# floppy_emul.net
KiCad netlist of a schematic drawn in EAGLE
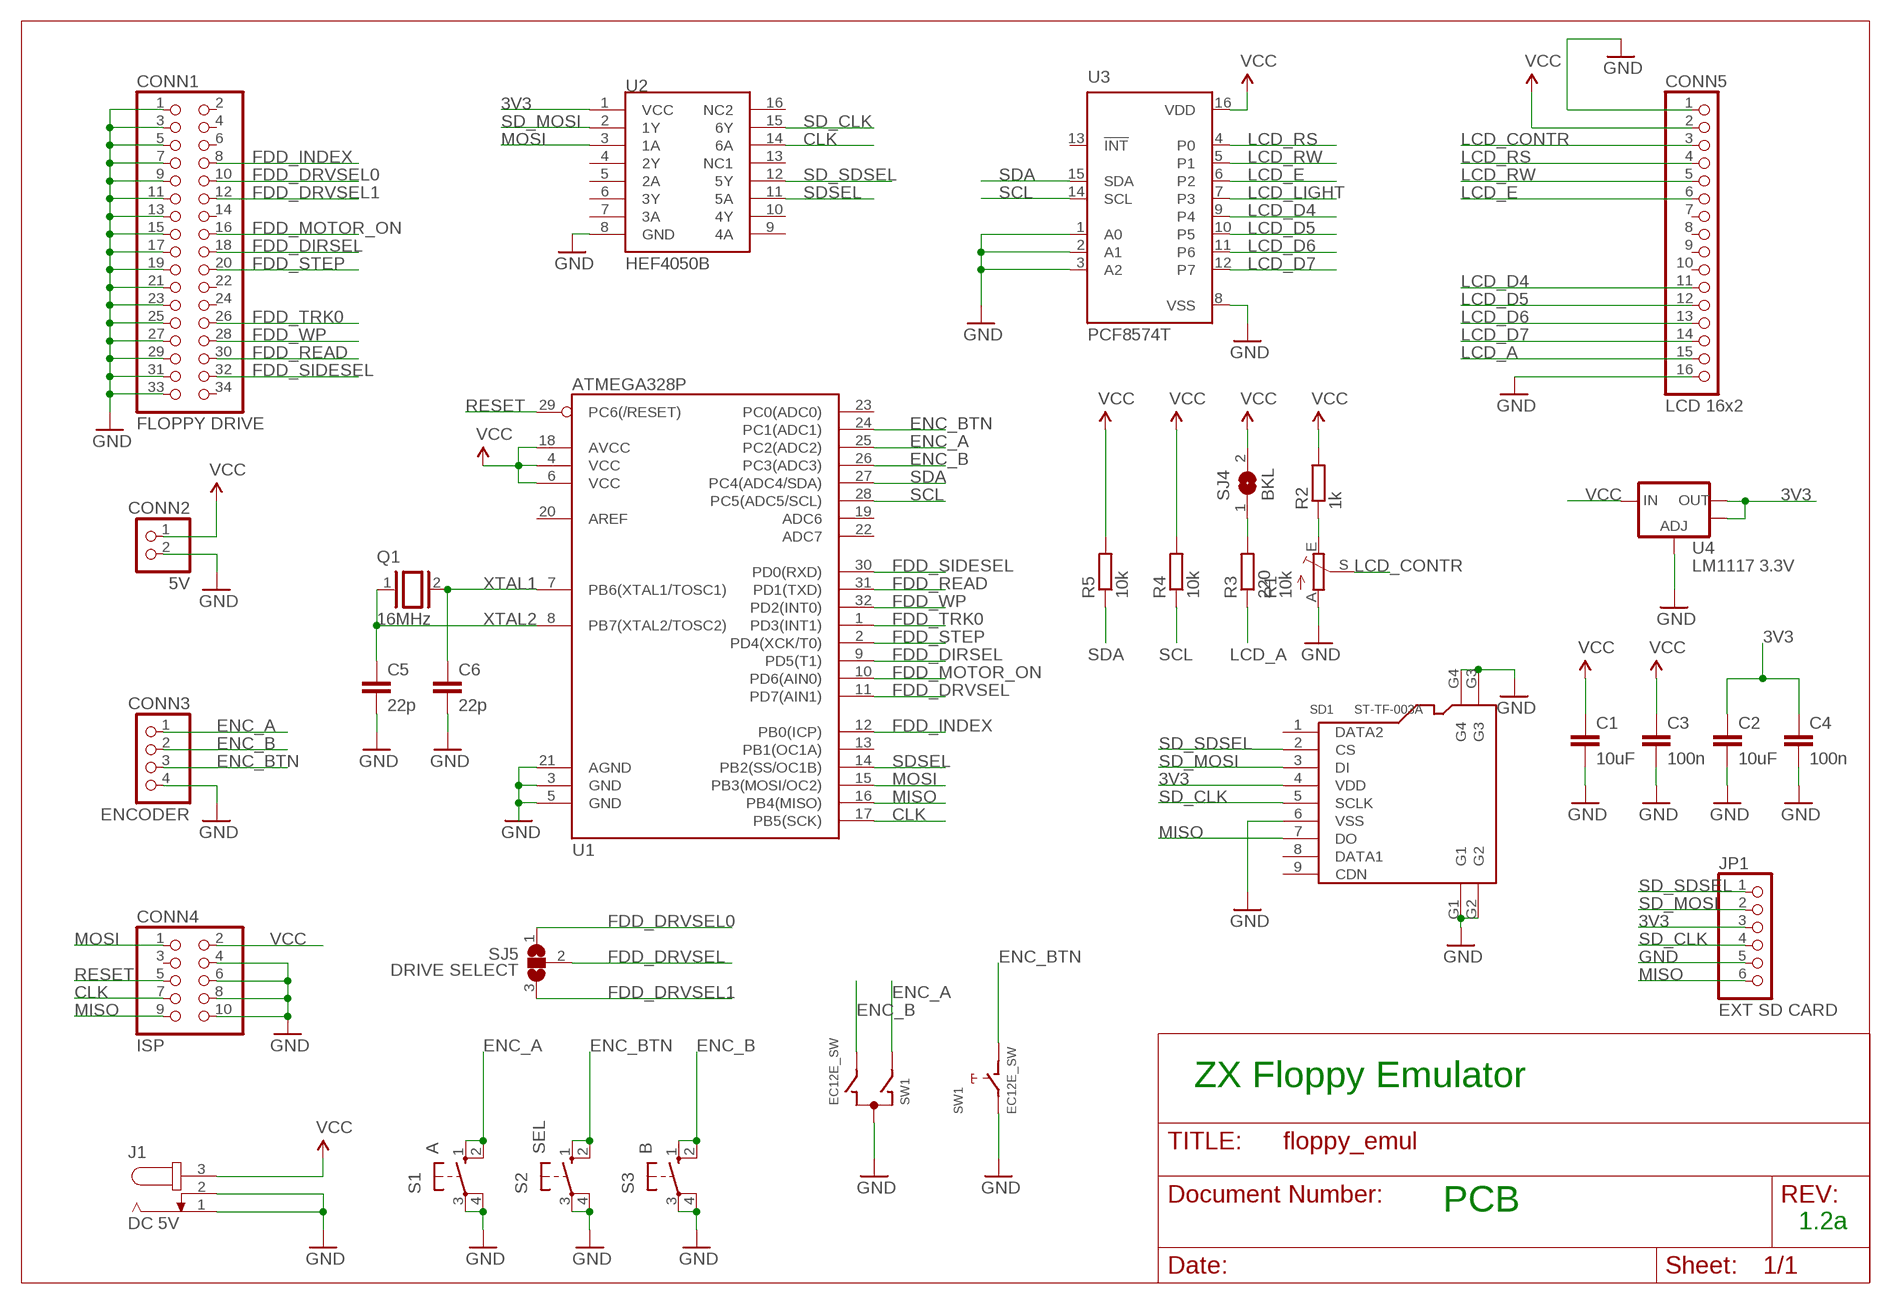
[diagram p0: schematic, sheet 1]

(export (version "E")
  (design (tool "Eeschema 10.0.6"))
  (components
    (comp (ref "C1")
      (value "10uF")
      (footprint "eagle-import:C0805")
      (libsource (lib "eagle-import") (part "C-EUC0805"))
    )
    (comp (ref "C2")
      (value "10uF")
      (footprint "eagle-import:C0805")
      (libsource (lib "eagle-import") (part "C-EUC0805"))
    )
    (comp (ref "C3")
      (value "100n")
      (footprint "eagle-import:C0805")
      (libsource (lib "eagle-import") (part "C-EUC0805"))
    )
    (comp (ref "C4")
      (value "100n")
      (footprint "eagle-import:C0805")
      (libsource (lib "eagle-import") (part "C-EUC0805"))
    )
    (comp (ref "C5")
      (value "22p")
      (footprint "eagle-import:C0805")
      (libsource (lib "eagle-import") (part "C-EUC0805"))
    )
    (comp (ref "C6")
      (value "22p")
      (footprint "eagle-import:C0805")
      (libsource (lib "eagle-import") (part "C-EUC0805"))
    )
    (comp (ref "CONN1")
      (value "FLOPPY DRIVE")
      (footprint "eagle-import:2X17")
      (libsource (lib "eagle-import") (part "PINHD-2X17"))
    )
    (comp (ref "CONN2")
      (value "5V")
      (footprint "eagle-import:1X02")
      (libsource (lib "eagle-import") (part "PINHD-1X2"))
    )
    (comp (ref "CONN3")
      (value "ENCODER")
      (footprint "eagle-import:1X04")
      (libsource (lib "eagle-import") (part "PINHD-1X4"))
    )
    (comp (ref "CONN4")
      (value "ISP")
      (footprint "eagle-import:2X05")
      (libsource (lib "eagle-import") (part "PINHD-2X5_2.54"))
    )
    (comp (ref "CONN5")
      (value "LCD 16x2")
      (footprint "eagle-import:1X16")
      (libsource (lib "eagle-import") (part "PINHD-1X16"))
    )
    (comp (ref "J1")
      (value "DC 5V")
      (footprint "eagle-import:SPC4077")
      (libsource (lib "eagle-import") (part "JACK-PLUG0"))
    )
    (comp (ref "JP1")
      (value "EXT SD CARD")
      (footprint "eagle-import:1X06")
      (libsource (lib "eagle-import") (part "PINHD-1X6"))
    )
    (comp (ref "Q1")
      (value "16MHz")
      (footprint "eagle-import:QS")
      (libsource (lib "eagle-import") (part "XTAL/S"))
    )
    (comp (ref "R1")
      (value "10k")
      (footprint "eagle-import:RJ9W")
      (libsource (lib "eagle-import") (part "TRIM_EU-RJ9W"))
    )
    (comp (ref "R2")
      (value "1k")
      (footprint "eagle-import:R0805")
      (libsource (lib "eagle-import") (part "R-EU_R0805"))
    )
    (comp (ref "R3")
      (value "220")
      (footprint "eagle-import:R0805")
      (libsource (lib "eagle-import") (part "R-EU_R0805"))
    )
    (comp (ref "R4")
      (value "10k")
      (footprint "eagle-import:R0805")
      (libsource (lib "eagle-import") (part "R-EU_R0805"))
    )
    (comp (ref "R5")
      (value "10k")
      (footprint "eagle-import:R0805")
      (libsource (lib "eagle-import") (part "R-EU_R0805"))
    )
    (comp (ref "S1")
      (value "A")
      (footprint "eagle-import:B3F-10XX")
      (fields (field (name "MPN") "B3F-1000"))
      (libsource (lib "eagle-import") (part "10-XX"))
    )
    (comp (ref "S2")
      (value "SEL")
      (footprint "eagle-import:B3F-10XX")
      (fields (field (name "MPN") "B3F-1000"))
      (libsource (lib "eagle-import") (part "10-XX"))
    )
    (comp (ref "S3")
      (value "B")
      (footprint "eagle-import:B3F-10XX")
      (fields (field (name "MPN") "B3F-1000"))
      (libsource (lib "eagle-import") (part "10-XX"))
    )
    (comp (ref "SD1")
      (value "ST-TF-003A")
      (footprint "eagle-import:MICRO-SD9+4P-SMD-16.1X14.5X1.85MM")
      (libsource (lib "eagle-import") (part "MICRO-SD-CARD-SOCKET-9P(ST-TF-003A)"))
    )
    (comp (ref "SJ4")
      (value "BKL")
      (footprint "eagle-import:SJ")
      (libsource (lib "eagle-import") (part "SJ"))
    )
    (comp (ref "SJ5")
      (value "DRIVE SELECT")
      (footprint "eagle-import:SJ_2")
      (libsource (lib "eagle-import") (part "SJ2W"))
    )
    (comp (ref "SW1")
      (value "EC12E_SW")
      (footprint "eagle-import:ALPS_EC12E_SW")
      (fields (field (name "MPN") "EC12E2424407"))
      (libsource (lib "eagle-import") (part "EC12E_SW"))
    )
    (comp (ref "U1")
      (value "ATMEGA328P")
      (footprint "eagle-import:TQFP32-08")
      (libsource (lib "eagle-import") (part "ATMEGA328_SMT"))
    )
    (comp (ref "U2")
      (value "HEF4050B")
      (footprint "eagle-import:SO16")
      (libsource (lib "eagle-import") (part "HEF4050BSO16"))
    )
    (comp (ref "U3")
      (value "PCF8574T")
      (footprint "eagle-import:SO16W")
      (fields (field (name "MPN") "PCF8574T/3,512"))
      (libsource (lib "eagle-import") (part "PCF8574T"))
    )
    (comp (ref "U4")
      (value "LM1117 3.3V")
      (footprint "eagle-import:SOT223")
      (libsource (lib "eagle-import") (part "V_REG_LM1117SOT223"))
    )
  )
  (nets
    (net (code "1") (name "/3V3") (class "Default")
      (node (ref "C2") (pin "1") (pinfunction "1_1") (pintype "passive"))
      (node (ref "C4") (pin "1") (pinfunction "1_1") (pintype "passive"))
      (node (ref "JP1") (pin "3") (pinfunction "3_3") (pintype "passive"))
      (node (ref "SD1") (pin "4") (pinfunction "VDD_4") (pintype "bidirectional"))
      (node (ref "U2") (pin "1") (pinfunction "VCC_1") (pintype "power_in"))
      (node (ref "U4") (pin "2") (pinfunction "OUT_2") (pintype "output"))
      (node (ref "U4") (pin "4") (pinfunction "OUT_4") (pintype "output"))
    )
    (net (code "2") (name "/CLK") (class "Default")
      (node (ref "CONN4") (pin "7") (pinfunction "7_7") (pintype "passive"))
      (node (ref "U1") (pin "17") (pinfunction "PB5(SCK)_17") (pintype "bidirectional"))
      (node (ref "U2") (pin "14") (pinfunction "6A_14") (pintype "input"))
    )
    (net (code "3") (name "/ENC_A") (class "Default")
      (node (ref "CONN3") (pin "1") (pinfunction "1_1") (pintype "passive"))
      (node (ref "S1") (pin "1") (pinfunction "S_1") (pintype "passive"))
      (node (ref "S1") (pin "2") (pinfunction "S1_2") (pintype "passive"))
      (node (ref "SW1") (pin "A") (pinfunction "A_A") (pintype "passive"))
      (node (ref "U1") (pin "25") (pinfunction "PC2(ADC2)_25") (pintype "bidirectional"))
    )
    (net (code "4") (name "/ENC_B") (class "Default")
      (node (ref "CONN3") (pin "2") (pinfunction "2_2") (pintype "passive"))
      (node (ref "S3") (pin "1") (pinfunction "S_1") (pintype "passive"))
      (node (ref "S3") (pin "2") (pinfunction "S1_2") (pintype "passive"))
      (node (ref "SW1") (pin "B") (pinfunction "B_B") (pintype "passive"))
      (node (ref "U1") (pin "26") (pinfunction "PC3(ADC3)_26") (pintype "bidirectional"))
    )
    (net (code "5") (name "/ENC_BTN") (class "Default")
      (node (ref "CONN3") (pin "3") (pinfunction "3_3") (pintype "passive"))
      (node (ref "S2") (pin "1") (pinfunction "S_1") (pintype "passive"))
      (node (ref "S2") (pin "2") (pinfunction "S1_2") (pintype "passive"))
      (node (ref "SW1") (pin "D") (pinfunction "1_D") (pintype "passive"))
      (node (ref "U1") (pin "24") (pinfunction "PC1(ADC1)_24") (pintype "bidirectional"))
    )
    (net (code "6") (name "/FDD_DIRSEL") (class "Default")
      (node (ref "CONN1") (pin "18") (pinfunction "18_18") (pintype "passive"))
      (node (ref "U1") (pin "9") (pinfunction "PD5(T1)_9") (pintype "bidirectional"))
    )
    (net (code "7") (name "/FDD_DRVSEL") (class "Default")
      (node (ref "SJ5") (pin "2") (pinfunction "2_2") (pintype "passive"))
      (node (ref "U1") (pin "11") (pinfunction "PD7(AIN1)_11") (pintype "bidirectional"))
    )
    (net (code "8") (name "/FDD_DRVSEL0") (class "Default")
      (node (ref "CONN1") (pin "10") (pinfunction "10_10") (pintype "passive"))
      (node (ref "SJ5") (pin "1") (pinfunction "1_1") (pintype "passive"))
    )
    (net (code "9") (name "/FDD_DRVSEL1") (class "Default")
      (node (ref "CONN1") (pin "12") (pinfunction "12_12") (pintype "passive"))
      (node (ref "SJ5") (pin "3") (pinfunction "3_3") (pintype "passive"))
    )
    (net (code "10") (name "/FDD_INDEX") (class "Default")
      (node (ref "CONN1") (pin "8") (pinfunction "8_8") (pintype "passive"))
      (node (ref "U1") (pin "12") (pinfunction "PB0(ICP)_12") (pintype "bidirectional"))
    )
    (net (code "11") (name "/FDD_MOTOR_ON") (class "Default")
      (node (ref "CONN1") (pin "16") (pinfunction "16_16") (pintype "passive"))
      (node (ref "U1") (pin "10") (pinfunction "PD6(AIN0)_10") (pintype "bidirectional"))
    )
    (net (code "12") (name "/FDD_READ") (class "Default")
      (node (ref "CONN1") (pin "30") (pinfunction "30_30") (pintype "passive"))
      (node (ref "U1") (pin "31") (pinfunction "PD1(TXD)_31") (pintype "bidirectional"))
    )
    (net (code "13") (name "/FDD_SIDESEL") (class "Default")
      (node (ref "CONN1") (pin "32") (pinfunction "32_32") (pintype "passive"))
      (node (ref "U1") (pin "30") (pinfunction "PD0(RXD)_30") (pintype "bidirectional"))
    )
    (net (code "14") (name "/FDD_STEP") (class "Default")
      (node (ref "CONN1") (pin "20") (pinfunction "20_20") (pintype "passive"))
      (node (ref "U1") (pin "2") (pinfunction "PD4(XCK/T0)_2") (pintype "bidirectional"))
    )
    (net (code "15") (name "/FDD_TRK0") (class "Default")
      (node (ref "CONN1") (pin "26") (pinfunction "26_26") (pintype "passive"))
      (node (ref "U1") (pin "1") (pinfunction "PD3(INT1)_1") (pintype "bidirectional"))
    )
    (net (code "16") (name "/FDD_WP") (class "Default")
      (node (ref "CONN1") (pin "28") (pinfunction "28_28") (pintype "passive"))
      (node (ref "U1") (pin "32") (pinfunction "PD2(INT0)_32") (pintype "bidirectional"))
    )
    (net (code "17") (name "/LCD_A") (class "Default")
      (node (ref "CONN5") (pin "15") (pinfunction "15_15") (pintype "passive"))
      (node (ref "R3") (pin "1") (pinfunction "1_1") (pintype "passive"))
    )
    (net (code "18") (name "/LCD_CONTR") (class "Default")
      (node (ref "CONN5") (pin "3") (pinfunction "3_3") (pintype "passive"))
      (node (ref "R1") (pin "S") (pinfunction "S_S") (pintype "passive"))
    )
    (net (code "19") (name "/LCD_D4") (class "Default")
      (node (ref "CONN5") (pin "11") (pinfunction "11_11") (pintype "passive"))
      (node (ref "U3") (pin "9") (pinfunction "P4_9") (pintype "bidirectional"))
    )
    (net (code "20") (name "/LCD_D5") (class "Default")
      (node (ref "CONN5") (pin "12") (pinfunction "12_12") (pintype "passive"))
      (node (ref "U3") (pin "10") (pinfunction "P5_10") (pintype "bidirectional"))
    )
    (net (code "21") (name "/LCD_D6") (class "Default")
      (node (ref "CONN5") (pin "13") (pinfunction "13_13") (pintype "passive"))
      (node (ref "U3") (pin "11") (pinfunction "P6_11") (pintype "bidirectional"))
    )
    (net (code "22") (name "/LCD_D7") (class "Default")
      (node (ref "CONN5") (pin "14") (pinfunction "14_14") (pintype "passive"))
      (node (ref "U3") (pin "12") (pinfunction "P7_12") (pintype "bidirectional"))
    )
    (net (code "23") (name "/LCD_E") (class "Default")
      (node (ref "CONN5") (pin "6") (pinfunction "6_6") (pintype "passive"))
      (node (ref "U3") (pin "6") (pinfunction "P2_6") (pintype "bidirectional"))
    )
    (net (code "24") (name "/LCD_LIGHT") (class "Default")
      (node (ref "U3") (pin "7") (pinfunction "P3_7") (pintype "bidirectional"))
    )
    (net (code "25") (name "/LCD_RS") (class "Default")
      (node (ref "CONN5") (pin "4") (pinfunction "4_4") (pintype "passive"))
      (node (ref "U3") (pin "4") (pinfunction "P0_4") (pintype "bidirectional"))
    )
    (net (code "26") (name "/LCD_RW") (class "Default")
      (node (ref "CONN5") (pin "5") (pinfunction "5_5") (pintype "passive"))
      (node (ref "U3") (pin "5") (pinfunction "P1_5") (pintype "bidirectional"))
    )
    (net (code "27") (name "/MISO") (class "Default")
      (node (ref "CONN4") (pin "9") (pinfunction "9_9") (pintype "passive"))
      (node (ref "JP1") (pin "6") (pinfunction "6_6") (pintype "passive"))
      (node (ref "SD1") (pin "7") (pinfunction "DO_7") (pintype "bidirectional"))
      (node (ref "U1") (pin "16") (pinfunction "PB4(MISO)_16") (pintype "bidirectional"))
    )
    (net (code "28") (name "/MOSI") (class "Default")
      (node (ref "CONN4") (pin "1") (pinfunction "1_1") (pintype "passive"))
      (node (ref "U1") (pin "15") (pinfunction "PB3(MOSI/OC2)_15") (pintype "bidirectional"))
      (node (ref "U2") (pin "3") (pinfunction "1A_3") (pintype "input"))
    )
    (net (code "29") (name "/RESET") (class "Default")
      (node (ref "CONN4") (pin "5") (pinfunction "5_5") (pintype "passive"))
      (node (ref "U1") (pin "29") (pinfunction "PC6(/RESET)_29") (pintype "bidirectional"))
    )
    (net (code "30") (name "/SCL") (class "Default")
      (node (ref "R4") (pin "1") (pinfunction "1_1") (pintype "passive"))
      (node (ref "U1") (pin "28") (pinfunction "PC5(ADC5/SCL)_28") (pintype "bidirectional"))
      (node (ref "U3") (pin "14") (pinfunction "SCL_14") (pintype "input"))
    )
    (net (code "31") (name "/SDA") (class "Default")
      (node (ref "R5") (pin "1") (pinfunction "1_1") (pintype "passive"))
      (node (ref "U1") (pin "27") (pinfunction "PC4(ADC4/SDA)_27") (pintype "bidirectional"))
      (node (ref "U3") (pin "15") (pinfunction "SDA_15") (pintype "bidirectional"))
    )
    (net (code "32") (name "/SDSEL") (class "Default")
      (node (ref "U1") (pin "14") (pinfunction "PB2(SS/OC1B)_14") (pintype "bidirectional"))
      (node (ref "U2") (pin "11") (pinfunction "5A_11") (pintype "input"))
    )
    (net (code "33") (name "/SD_CLK") (class "Default")
      (node (ref "JP1") (pin "4") (pinfunction "4_4") (pintype "passive"))
      (node (ref "SD1") (pin "5") (pinfunction "SCLK_5") (pintype "bidirectional"))
      (node (ref "U2") (pin "15") (pinfunction "6Y_15") (pintype "output"))
    )
    (net (code "34") (name "/SD_MOSI") (class "Default")
      (node (ref "JP1") (pin "2") (pinfunction "2_2") (pintype "passive"))
      (node (ref "SD1") (pin "3") (pinfunction "DI_3") (pintype "bidirectional"))
      (node (ref "U2") (pin "2") (pinfunction "1Y_2") (pintype "output"))
    )
    (net (code "35") (name "/SD_SDSEL") (class "Default")
      (node (ref "JP1") (pin "1") (pinfunction "1_1") (pintype "passive"))
      (node (ref "SD1") (pin "2") (pinfunction "CS_2") (pintype "bidirectional"))
      (node (ref "U2") (pin "12") (pinfunction "5Y_12") (pintype "output"))
    )
    (net (code "36") (name "/XTAL1") (class "Default")
      (node (ref "C6") (pin "1") (pinfunction "1_1") (pintype "passive"))
      (node (ref "Q1") (pin "2") (pinfunction "2_2") (pintype "passive"))
      (node (ref "U1") (pin "7") (pinfunction "PB6(XTAL1/TOSC1)_7") (pintype "bidirectional"))
    )
    (net (code "37") (name "/XTAL2") (class "Default")
      (node (ref "C5") (pin "1") (pinfunction "1_1") (pintype "passive"))
      (node (ref "Q1") (pin "1") (pinfunction "1_1") (pintype "passive"))
      (node (ref "U1") (pin "8") (pinfunction "PB7(XTAL2/TOSC2)_8") (pintype "bidirectional"))
    )
    (net (code "38") (name "GND") (class "Default")
      (node (ref "C1") (pin "2") (pinfunction "2_2") (pintype "passive"))
      (node (ref "C2") (pin "2") (pinfunction "2_2") (pintype "passive"))
      (node (ref "C3") (pin "2") (pinfunction "2_2") (pintype "passive"))
      (node (ref "C4") (pin "2") (pinfunction "2_2") (pintype "passive"))
      (node (ref "C5") (pin "2") (pinfunction "2_2") (pintype "passive"))
      (node (ref "C6") (pin "2") (pinfunction "2_2") (pintype "passive"))
      (node (ref "CONN1") (pin "1") (pinfunction "1_1") (pintype "passive"))
      (node (ref "CONN1") (pin "11") (pinfunction "11_11") (pintype "passive"))
      (node (ref "CONN1") (pin "13") (pinfunction "13_13") (pintype "passive"))
      (node (ref "CONN1") (pin "15") (pinfunction "15_15") (pintype "passive"))
      (node (ref "CONN1") (pin "17") (pinfunction "17_17") (pintype "passive"))
      (node (ref "CONN1") (pin "19") (pinfunction "19_19") (pintype "passive"))
      (node (ref "CONN1") (pin "21") (pinfunction "21_21") (pintype "passive"))
      (node (ref "CONN1") (pin "23") (pinfunction "23_23") (pintype "passive"))
      (node (ref "CONN1") (pin "25") (pinfunction "25_25") (pintype "passive"))
      (node (ref "CONN1") (pin "27") (pinfunction "27_27") (pintype "passive"))
      (node (ref "CONN1") (pin "29") (pinfunction "29_29") (pintype "passive"))
      (node (ref "CONN1") (pin "3") (pinfunction "3_3") (pintype "passive"))
      (node (ref "CONN1") (pin "31") (pinfunction "31_31") (pintype "passive"))
      (node (ref "CONN1") (pin "33") (pinfunction "33_33") (pintype "passive"))
      (node (ref "CONN1") (pin "5") (pinfunction "5_5") (pintype "passive"))
      (node (ref "CONN1") (pin "7") (pinfunction "7_7") (pintype "passive"))
      (node (ref "CONN1") (pin "9") (pinfunction "9_9") (pintype "passive"))
      (node (ref "CONN2") (pin "2") (pinfunction "2_2") (pintype "passive"))
      (node (ref "CONN3") (pin "4") (pinfunction "4_4") (pintype "passive"))
      (node (ref "CONN4") (pin "10") (pinfunction "10_10") (pintype "passive"))
      (node (ref "CONN4") (pin "4") (pinfunction "4_4") (pintype "passive"))
      (node (ref "CONN4") (pin "6") (pinfunction "6_6") (pintype "passive"))
      (node (ref "CONN4") (pin "8") (pinfunction "8_8") (pintype "passive"))
      (node (ref "CONN5") (pin "1") (pinfunction "1_1") (pintype "passive"))
      (node (ref "CONN5") (pin "16") (pinfunction "16_16") (pintype "passive"))
      (node (ref "J1") (pin "1") (pinfunction "1_1") (pintype "passive"))
      (node (ref "J1") (pin "2") (pinfunction "2_2") (pintype "passive"))
      (node (ref "JP1") (pin "5") (pinfunction "5_5") (pintype "passive"))
      (node (ref "R1") (pin "A") (pinfunction "A_A") (pintype "passive"))
      (node (ref "S1") (pin "3") (pinfunction "P_3") (pintype "passive"))
      (node (ref "S1") (pin "4") (pinfunction "P1_4") (pintype "passive"))
      (node (ref "S2") (pin "3") (pinfunction "P_3") (pintype "passive"))
      (node (ref "S2") (pin "4") (pinfunction "P1_4") (pintype "passive"))
      (node (ref "S3") (pin "3") (pinfunction "P_3") (pintype "passive"))
      (node (ref "S3") (pin "4") (pinfunction "P1_4") (pintype "passive"))
      (node (ref "SD1") (pin "6") (pinfunction "VSS_6") (pintype "bidirectional"))
      (node (ref "SD1") (pin "G1") (pinfunction "G1_G1") (pintype "bidirectional"))
      (node (ref "SD1") (pin "G2") (pinfunction "G2_G2") (pintype "bidirectional"))
      (node (ref "SD1") (pin "G3") (pinfunction "G3_G3") (pintype "bidirectional"))
      (node (ref "SD1") (pin "G4") (pinfunction "G4_G4") (pintype "bidirectional"))
      (node (ref "SW1") (pin "C") (pinfunction "C_C") (pintype "passive"))
      (node (ref "SW1") (pin "E") (pinfunction "2_E") (pintype "passive"))
      (node (ref "U1") (pin "21") (pinfunction "AGND_21") (pintype "bidirectional"))
      (node (ref "U1") (pin "3") (pinfunction "GND_3") (pintype "bidirectional"))
      (node (ref "U1") (pin "5") (pinfunction "GND_5") (pintype "bidirectional"))
      (node (ref "U2") (pin "8") (pinfunction "GND_8") (pintype "power_in"))
      (node (ref "U3") (pin "1") (pinfunction "A0_1") (pintype "input"))
      (node (ref "U3") (pin "2") (pinfunction "A1_2") (pintype "input"))
      (node (ref "U3") (pin "3") (pinfunction "A2_3") (pintype "input"))
      (node (ref "U3") (pin "8") (pinfunction "VSS_8") (pintype "power_in"))
      (node (ref "U4") (pin "1") (pinfunction "ADJ_1") (pintype "input"))
    )
    (net (code "39") (name "Net-(R1-PadE)") (class "Default")
      (node (ref "R1") (pin "E") (pinfunction "E_E") (pintype "passive"))
      (node (ref "R2") (pin "1") (pinfunction "1_1") (pintype "passive"))
    )
    (net (code "40") (name "Net-(R3-Pad2)") (class "Default")
      (node (ref "R3") (pin "2") (pinfunction "2_2") (pintype "passive"))
      (node (ref "SJ4") (pin "1") (pinfunction "1_1") (pintype "passive"))
    )
    (net (code "41") (name "VCC") (class "Default")
      (node (ref "C1") (pin "1") (pinfunction "1_1") (pintype "passive"))
      (node (ref "C3") (pin "1") (pinfunction "1_1") (pintype "passive"))
      (node (ref "CONN2") (pin "1") (pinfunction "1_1") (pintype "passive"))
      (node (ref "CONN4") (pin "2") (pinfunction "2_2") (pintype "passive"))
      (node (ref "CONN5") (pin "2") (pinfunction "2_2") (pintype "passive"))
      (node (ref "J1") (pin "3") (pinfunction "3_3") (pintype "passive"))
      (node (ref "R2") (pin "2") (pinfunction "2_2") (pintype "passive"))
      (node (ref "R4") (pin "2") (pinfunction "2_2") (pintype "passive"))
      (node (ref "R5") (pin "2") (pinfunction "2_2") (pintype "passive"))
      (node (ref "SJ4") (pin "2") (pinfunction "2_2") (pintype "passive"))
      (node (ref "U1") (pin "18") (pinfunction "AVCC_18") (pintype "bidirectional"))
      (node (ref "U1") (pin "4") (pinfunction "VCC_4") (pintype "bidirectional"))
      (node (ref "U1") (pin "6") (pinfunction "VCC_6") (pintype "bidirectional"))
      (node (ref "U3") (pin "16") (pinfunction "VDD_16") (pintype "power_in"))
      (node (ref "U4") (pin "3") (pinfunction "IN_3") (pintype "input"))
    )
    (net (code "42") (name "unconnected-(CONN1-Pad2)") (class "Default")
      (node (ref "CONN1") (pin "2") (pinfunction "2_2") (pintype "passive"))
    )
    (net (code "43") (name "unconnected-(CONN1-Pad4)") (class "Default")
      (node (ref "CONN1") (pin "4") (pinfunction "4_4") (pintype "passive"))
    )
    (net (code "44") (name "unconnected-(CONN1-Pad6)") (class "Default")
      (node (ref "CONN1") (pin "6") (pinfunction "6_6") (pintype "passive"))
    )
    (net (code "45") (name "unconnected-(CONN1-Pad14)") (class "Default")
      (node (ref "CONN1") (pin "14") (pinfunction "14_14") (pintype "passive"))
    )
    (net (code "46") (name "unconnected-(CONN1-Pad22)") (class "Default")
      (node (ref "CONN1") (pin "22") (pinfunction "22_22") (pintype "passive"))
    )
    (net (code "47") (name "unconnected-(CONN1-Pad24)") (class "Default")
      (node (ref "CONN1") (pin "24") (pinfunction "24_24") (pintype "passive"))
    )
    (net (code "48") (name "unconnected-(CONN1-Pad34)") (class "Default")
      (node (ref "CONN1") (pin "34") (pinfunction "34_34") (pintype "passive"))
    )
    (net (code "49") (name "unconnected-(CONN4-Pad3)") (class "Default")
      (node (ref "CONN4") (pin "3") (pinfunction "3_3") (pintype "passive"))
    )
    (net (code "50") (name "unconnected-(CONN5-Pad7)") (class "Default")
      (node (ref "CONN5") (pin "7") (pinfunction "7_7") (pintype "passive"))
    )
    (net (code "51") (name "unconnected-(CONN5-Pad8)") (class "Default")
      (node (ref "CONN5") (pin "8") (pinfunction "8_8") (pintype "passive"))
    )
    (net (code "52") (name "unconnected-(CONN5-Pad9)") (class "Default")
      (node (ref "CONN5") (pin "9") (pinfunction "9_9") (pintype "passive"))
    )
    (net (code "53") (name "unconnected-(CONN5-Pad10)") (class "Default")
      (node (ref "CONN5") (pin "10") (pinfunction "10_10") (pintype "passive"))
    )
    (net (code "54") (name "unconnected-(SD1-CDN-Pad9)") (class "Default")
      (node (ref "SD1") (pin "9") (pinfunction "CDN_9") (pintype "bidirectional"))
    )
    (net (code "55") (name "unconnected-(SD1-DATA1-Pad8)") (class "Default")
      (node (ref "SD1") (pin "8") (pinfunction "DATA1_8") (pintype "bidirectional"))
    )
    (net (code "56") (name "unconnected-(SD1-DATA2-Pad1)") (class "Default")
      (node (ref "SD1") (pin "1") (pinfunction "DATA2_1") (pintype "bidirectional"))
    )
    (net (code "57") (name "unconnected-(U1-ADC6-Pad19)") (class "Default")
      (node (ref "U1") (pin "19") (pinfunction "ADC6_19") (pintype "bidirectional"))
    )
    (net (code "58") (name "unconnected-(U1-ADC7-Pad22)") (class "Default")
      (node (ref "U1") (pin "22") (pinfunction "ADC7_22") (pintype "bidirectional"))
    )
    (net (code "59") (name "unconnected-(U1-AREF-Pad20)") (class "Default")
      (node (ref "U1") (pin "20") (pinfunction "AREF_20") (pintype "bidirectional"))
    )
    (net (code "60") (name "unconnected-(U1-PB1(OC1A)-Pad13)") (class "Default")
      (node (ref "U1") (pin "13") (pinfunction "PB1(OC1A)_13") (pintype "bidirectional"))
    )
    (net (code "61") (name "unconnected-(U1-PC0(ADC0)-Pad23)") (class "Default")
      (node (ref "U1") (pin "23") (pinfunction "PC0(ADC0)_23") (pintype "bidirectional"))
    )
    (net (code "62") (name "unconnected-(U2-2A-Pad5)") (class "Default")
      (node (ref "U2") (pin "5") (pinfunction "2A_5") (pintype "input"))
    )
    (net (code "63") (name "unconnected-(U2-2Y-Pad4)") (class "Default")
      (node (ref "U2") (pin "4") (pinfunction "2Y_4") (pintype "output"))
    )
    (net (code "64") (name "unconnected-(U2-3A-Pad7)") (class "Default")
      (node (ref "U2") (pin "7") (pinfunction "3A_7") (pintype "input"))
    )
    (net (code "65") (name "unconnected-(U2-3Y-Pad6)") (class "Default")
      (node (ref "U2") (pin "6") (pinfunction "3Y_6") (pintype "output"))
    )
    (net (code "66") (name "unconnected-(U2-4A-Pad9)") (class "Default")
      (node (ref "U2") (pin "9") (pinfunction "4A_9") (pintype "input"))
    )
    (net (code "67") (name "unconnected-(U2-4Y-Pad10)") (class "Default")
      (node (ref "U2") (pin "10") (pinfunction "4Y_10") (pintype "output"))
    )
    (net (code "68") (name "unconnected-(U2-NC1-Pad13)") (class "Default")
      (node (ref "U2") (pin "13") (pinfunction "NC1_13") (pintype "no_connect"))
    )
    (net (code "69") (name "unconnected-(U2-NC2-Pad16)") (class "Default")
      (node (ref "U2") (pin "16") (pinfunction "NC2_16") (pintype "no_connect"))
    )
    (net (code "70") (name "unconnected-(U3-~{INT}-Pad13)") (class "Default")
      (node (ref "U3") (pin "13") (pinfunction "~{INT}_13") (pintype "output"))
    )
  )
)
